# OnOffSolenoid.net
KiCad netlist of a schematic drawn in Altium Designer
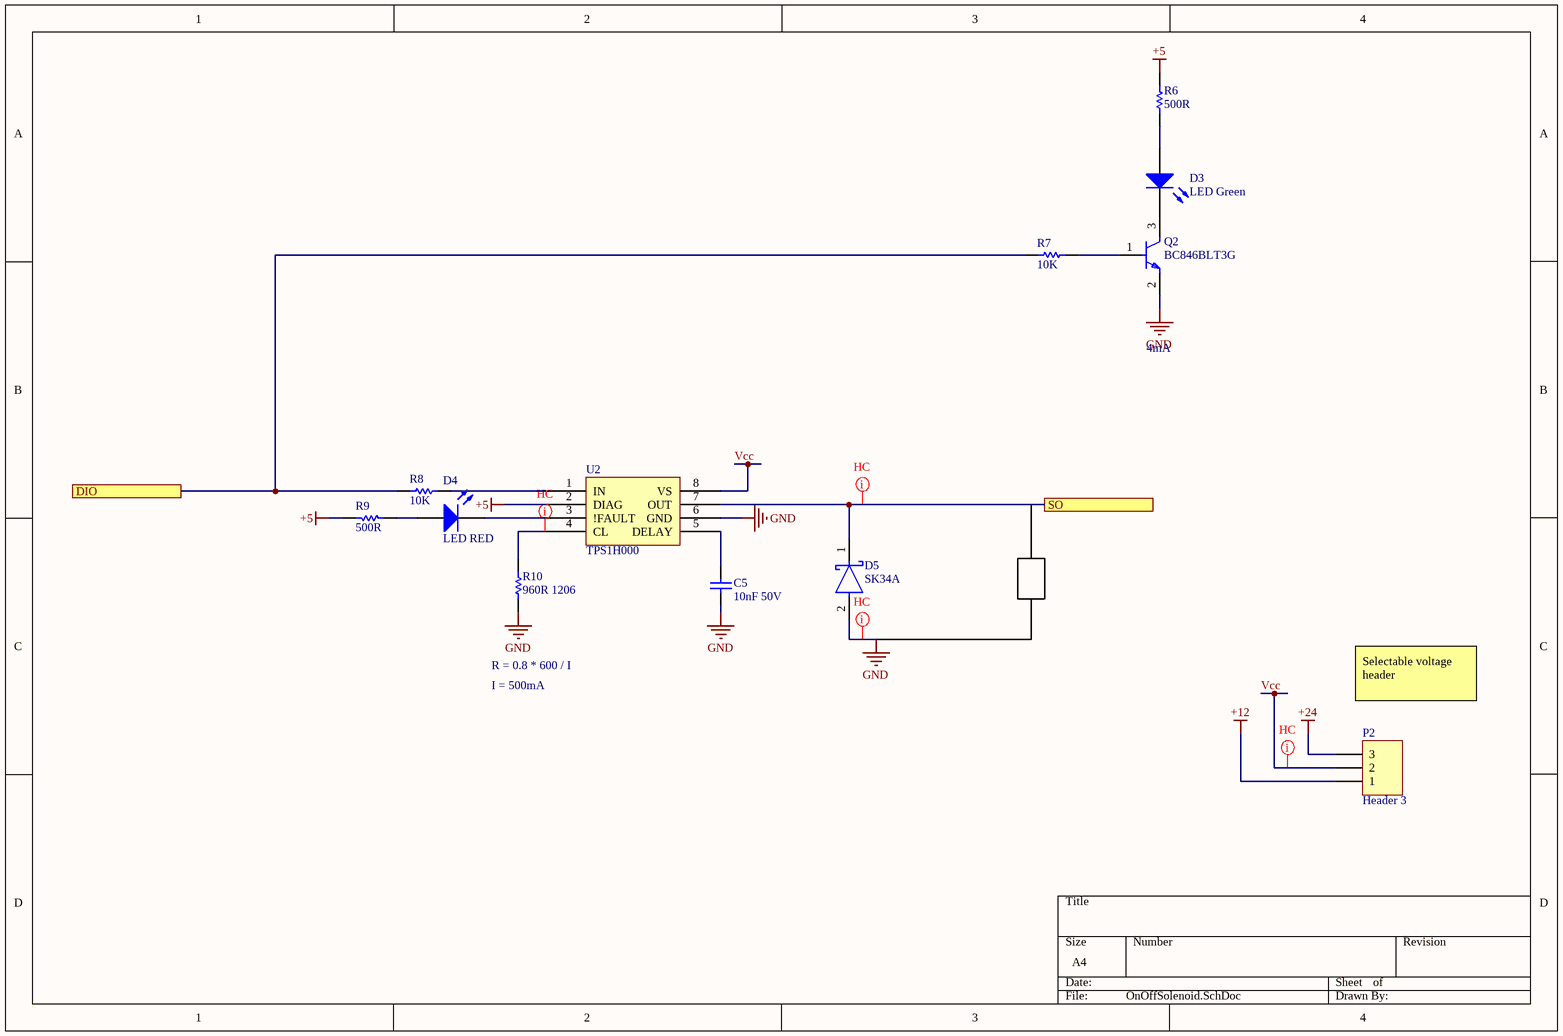
[diagram p0: OnOffSolenoid.SchDoc]

(export (version "E")
  (design (tool "Eeschema 10.0.6"))
  (components
    (comp (ref "C5")
      (value "10nF 50V")
      (footprint "CAPC0603(1608)100_L")
      (description "CAP 10nF 50V ±20% 0603 (1608 Metric) Thickness 1mm SMD")
      (fields (field (name "TOLERANCE") "Â±20%"))
      (libsource (lib "Altium Content Vault") (part "CAP"))
    )
    (comp (ref "D3")
      (value "LED Green")
      (footprint "0603_A")
      (description "SMD mono-color Chip LED, WL-SMCW, Green")
      (fields (field (name "PARTNUMBER") "150060GS75000") (field (name "MANUFACTURER") "Wuerth Elektronik"))
      (libsource (lib "Altium Content Vault") (part "WE-LED_K1A2-2"))
    )
    (comp (ref "D4")
      (value "LED RED")
      (footprint "0603_A")
      (description "SMD mono-color Chip LED, WL-SMCW, Red")
      (fields (field (name "MANUFACTURER") "Wuerth Elektronik") (field (name "PARTNUMBER") "150060RS75000"))
      (libsource (lib "Altium Content Vault") (part "WE-LED_K1A2-2"))
    )
    (comp (ref "D5")
      (value "SK34A")
      (footprint "FP-DO-214AC-MFG")
      (description "DIODE SCHOTTKY 5A 30V SMA")
      (libsource (lib "Altium Content Vault") (part "1d6ec82d83fb6aee721767c19dac4b9"))
    )
    (comp (ref "P2")
      (value "Header 3")
      (footprint "HDR1X3")
      (description "Header, 3-Pin")
      (fields (field (name "PUBLISHER") "Altium Limited"))
      (libsource (lib "Miscellaneous Connectors") (part "Header 3"))
    )
    (comp (ref "Q2")
      (value "BC846BLT3G")
      (footprint "FP-318-08-IPC_C")
      (description "TRANS NPN 65V 0.1A SOT-23")
      (libsource (lib "Altium Content Vault") (part "2a1388f82443b098dcd57d24ac7632d"))
    )
    (comp (ref "R6")
      (value "500R")
      (footprint "RESC0603(1608)_L")
      (description "510R 0.1W 5% 0603 (1608 Metric)  SMD")
      (fields (field (name "POWER") "0.1 W") (field (name "TOLERANCE") "5 %"))
      (libsource (lib "Altium Content Vault") (part "RES"))
    )
    (comp (ref "R7")
      (value "10K")
      (footprint "RESC0603(1608)_N")
      (description "10K 0.1W 1% 0603 (1608 Metric)  SMD")
      (fields (field (name "POWER") "0.1 W") (field (name "TOLERANCE") "1 %"))
      (libsource (lib "Altium Content Vault") (part "RES"))
    )
    (comp (ref "R8")
      (value "10K")
      (footprint "RESC0603(1608)_N")
      (description "10K 0.1W 1% 0603 (1608 Metric)  SMD")
      (fields (field (name "POWER") "0.1 W") (field (name "TOLERANCE") "1 %"))
      (libsource (lib "Altium Content Vault") (part "RES"))
    )
    (comp (ref "R9")
      (value "500R")
      (footprint "RESC0603(1608)_L")
      (description "510R 0.1W 5% 0603 (1608 Metric)  SMD")
      (fields (field (name "POWER") "0.1 W") (field (name "TOLERANCE") "5 %"))
      (libsource (lib "Altium Content Vault") (part "RES"))
    )
    (comp (ref "R10")
      (value "960R 1206")
      (footprint "RESC1206(3216)_L")
      (description "953R 0.25W 1% 1206 (3216 Metric)  SMD")
      (fields (field (name "TOLERANCE") "1 %") (field (name "POWER") "0.25 W"))
      (libsource (lib "Altium Content Vault") (part "RES"))
    )
    (comp (ref "U2")
      (value "TPS1H000")
      (footprint "TSOP65P490X110_HS-9N")
      (libsource (lib "Schlib1") (part "TPS1H000"))
    )
  )
  (nets
    (net (code "1") (name "+5") (class "Default")
      (node (ref "R6") (pin "2") (pinfunction "2_2") (pintype "passive"))
      (node (ref "R9") (pin "2") (pinfunction "2_2") (pintype "passive"))
      (node (ref "U2") (pin "2") (pinfunction "DIAG_2") (pintype "passive"))
    )
    (net (code "2") (name "+12") (class "Default")
      (node (ref "P2") (pin "1") (pinfunction "1_1") (pintype "passive"))
    )
    (net (code "3") (name "+24") (class "Default")
      (node (ref "P2") (pin "3") (pinfunction "3_3") (pintype "passive"))
    )
    (net (code "4") (name "/DIO") (class "Default")
      (node (ref "R7") (pin "1") (pinfunction "1_1") (pintype "passive"))
      (node (ref "R8") (pin "1") (pinfunction "1_1") (pintype "passive"))
    )
    (net (code "5") (name "/SO") (class "Default")
      (node (ref "D5") (pin "1") (pinfunction "C_1") (pintype "passive"))
      (node (ref "U2") (pin "7") (pinfunction "OUT_7") (pintype "passive"))
    )
    (net (code "6") (name "/Vcc") (class "Default")
      (node (ref "P2") (pin "2") (pinfunction "2_2") (pintype "passive"))
      (node (ref "U2") (pin "8") (pinfunction "VS_8") (pintype "passive"))
    )
    (net (code "7") (name "GND") (class "Default")
      (node (ref "C5") (pin "1") (pinfunction "1_1") (pintype "passive"))
      (node (ref "D5") (pin "2") (pinfunction "A_2") (pintype "passive"))
      (node (ref "Q2") (pin "2") (pinfunction "E_2") (pintype "passive"))
      (node (ref "R10") (pin "1") (pinfunction "1_1") (pintype "passive"))
      (node (ref "U2") (pin "6") (pinfunction "GND_6") (pintype "passive"))
    )
    (net (code "8") (name "Net-(D3-A)") (class "Default")
      (node (ref "D3") (pin "2") (pinfunction "A_2") (pintype "passive"))
      (node (ref "R6") (pin "1") (pinfunction "1_1") (pintype "passive"))
    )
    (net (code "9") (name "Net-(D3-K)") (class "Default")
      (node (ref "D3") (pin "1") (pinfunction "K_1") (pintype "passive"))
      (node (ref "Q2") (pin "3") (pinfunction "C_3") (pintype "passive"))
    )
    (net (code "10") (name "Net-(D4-A)") (class "Default")
      (node (ref "D4") (pin "2") (pinfunction "A_2") (pintype "passive"))
      (node (ref "R9") (pin "1") (pinfunction "1_1") (pintype "passive"))
    )
    (net (code "11") (name "Net-(D4-K)") (class "Default")
      (node (ref "D4") (pin "1") (pinfunction "K_1") (pintype "passive"))
      (node (ref "U2") (pin "3") (pinfunction "!FAULT_3") (pintype "passive"))
    )
    (net (code "12") (name "Net-(Q2-B)") (class "Default")
      (node (ref "Q2") (pin "1") (pinfunction "B_1") (pintype "passive"))
      (node (ref "R7") (pin "2") (pinfunction "2_2") (pintype "passive"))
    )
    (net (code "13") (name "Net-(U2-CL)") (class "Default")
      (node (ref "R10") (pin "2") (pinfunction "2_2") (pintype "passive"))
      (node (ref "U2") (pin "4") (pinfunction "CL_4") (pintype "passive"))
    )
    (net (code "14") (name "Net-(U2-DELAY)") (class "Default")
      (node (ref "C5") (pin "2") (pinfunction "2_2") (pintype "passive"))
      (node (ref "U2") (pin "5") (pinfunction "DELAY_5") (pintype "passive"))
    )
    (net (code "15") (name "Net-(U2-IN)") (class "Default")
      (node (ref "R8") (pin "2") (pinfunction "2_2") (pintype "passive"))
      (node (ref "U2") (pin "1") (pinfunction "IN_1") (pintype "passive"))
    )
  )
)
